# driver0-3.net
KiCad netlist of a schematic drawn in Altium Designer
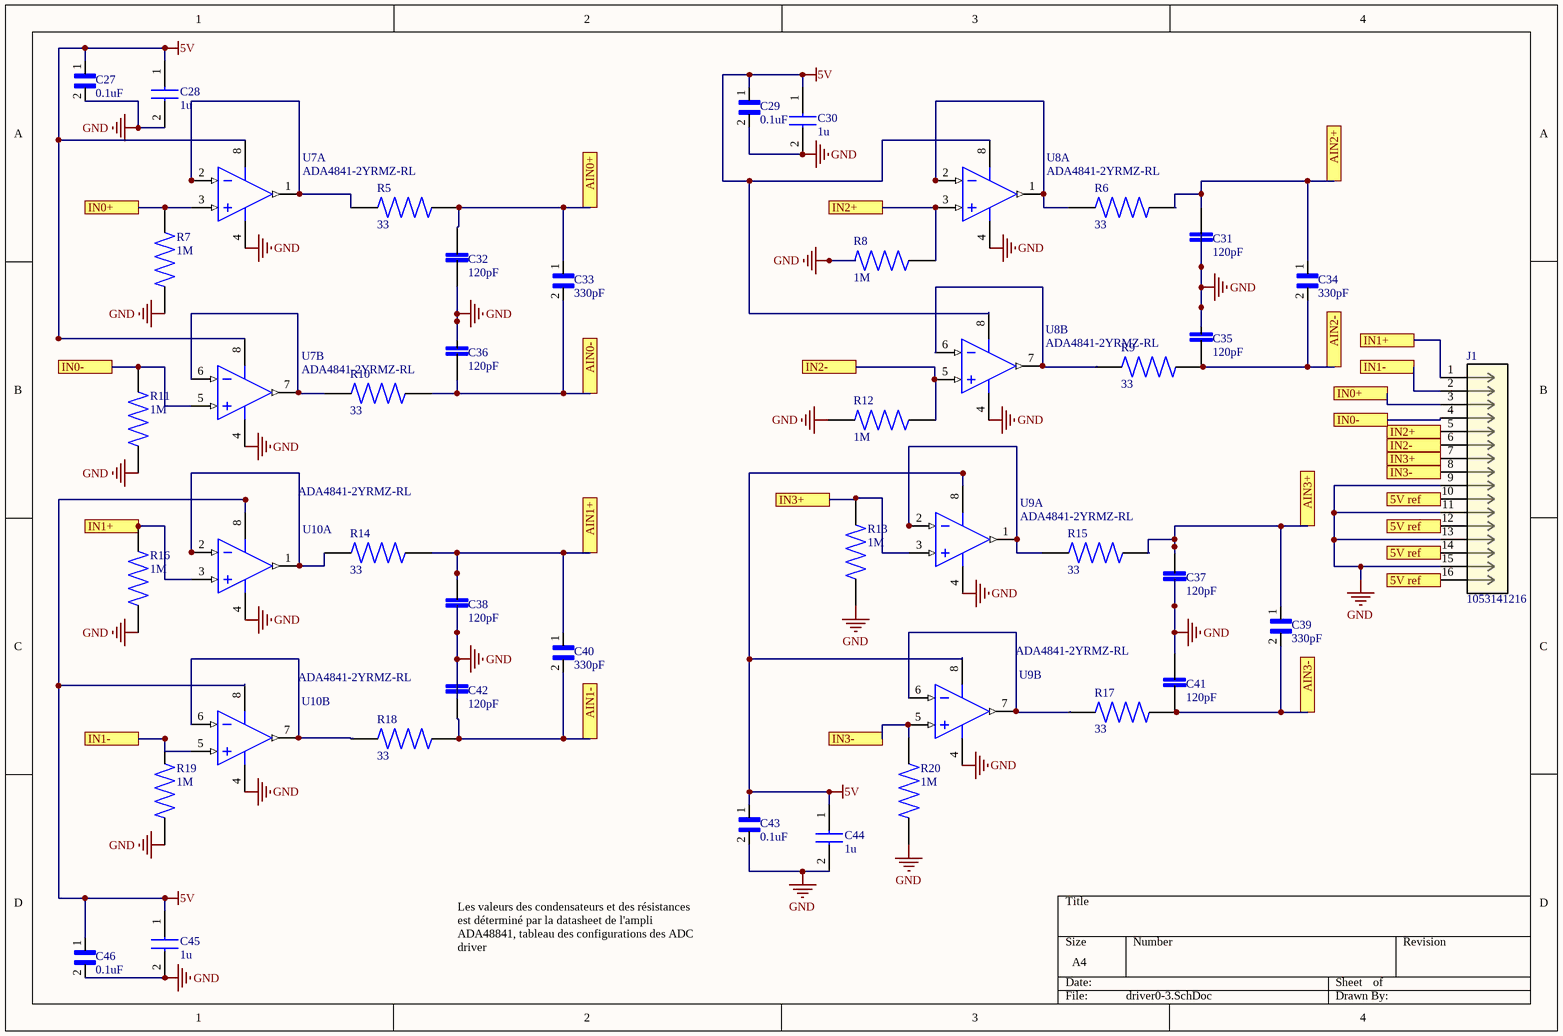
[diagram p0: driver0-3.SchDoc]

(export (version "E")
  (design (tool "Eeschema 10.0.6"))
  (components
    (comp (ref "C27")
      (value "0.1uF")
      (footprint "CAPC1608X90N")
      (description "Cap Ceramic 0.1uF 25V X5R 10% SMD 0603 85ÂÂŽ T/R")
      (fields
        (field (name "MP") "06033D104KAT2A")
        (field (name "MF") "{'manufacturer': u'AVX'}")
        (field (name "SOURCE") "workerBoard.SCHLIB")
      )
      (libsource (lib "GIGUL") (part "06033D104KAT2A"))
    )
    (comp (ref "C28")
      (value "1u")
      (footprint "CAPC1608X90N")
      (description "Capacitor")
      (fields
        (field (name "MANUFACTURER_PART_NUMBER") "0603YC105MAT4A")
        (field (name "SOURCE") "workerBoard.SCHLIB")
      )
      (libsource (lib "GIGUL") (part "0603YC105MAT4A"))
    )
    (comp (ref "C29")
      (value "0.1uF")
      (footprint "CAPC1608X90N")
      (description "Cap Ceramic 0.1uF 25V X5R 10% SMD 0603 85ÂÂŽ T/R")
      (fields
        (field (name "MP") "06033D104KAT2A")
        (field (name "MF") "{'manufacturer': u'AVX'}")
        (field (name "SOURCE") "workerBoard.SCHLIB")
      )
      (libsource (lib "GIGUL") (part "06033D104KAT2A"))
    )
    (comp (ref "C30")
      (value "1u")
      (footprint "CAPC1608X90N")
      (description "Capacitor")
      (fields
        (field (name "MANUFACTURER_PART_NUMBER") "0603YC105MAT4A")
        (field (name "SOURCE") "workerBoard.SCHLIB")
      )
      (libsource (lib "GIGUL") (part "0603YC105MAT4A"))
    )
    (comp (ref "C31")
      (value "120pF")
      (footprint "CAPC1608X90")
      (description "0603 120 pF 50 V Â±2 % Tolerance C0G/NP0 SMT Multilayer Ceramic Capacitor")
      (fields
        (field (name "MP") "06035A121GAT2A")
        (field (name "MF") "{'manufacturer': u'AVX'}")
        (field (name "SOURCE") "workerBoard.SCHLIB")
      )
      (libsource (lib "GIGUL") (part "06035A121GAT2A"))
    )
    (comp (ref "C32")
      (value "120pF")
      (footprint "CAPC1608X90")
      (description "0603 120 pF 50 V Â±2 % Tolerance C0G/NP0 SMT Multilayer Ceramic Capacitor")
      (fields
        (field (name "MP") "06035A121GAT2A")
        (field (name "MF") "{'manufacturer': u'AVX'}")
        (field (name "SOURCE") "workerBoard.SCHLIB")
      )
      (libsource (lib "GIGUL") (part "06035A121GAT2A"))
    )
    (comp (ref "C33")
      (value "330pF")
      (footprint "CAPC1608X90")
      (description "0603 SMD Ceramic Capacitors 0603 330pF 25volts C0G 2%")
      (fields
        (field (name "MP") "06033A331GAT2A")
        (field (name "MF") "{'manufacturer': u'AVX'}")
        (field (name "SOURCE") "workerBoard.SCHLIB")
      )
      (libsource (lib "") (part "Symbol_1"))
    )
    (comp (ref "C34")
      (value "330pF")
      (footprint "CAPC1608X90")
      (description "0603 SMD Ceramic Capacitors 0603 330pF 25volts C0G 2%")
      (fields
        (field (name "MP") "06033A331GAT2A")
        (field (name "MF") "{'manufacturer': u'AVX'}")
        (field (name "SOURCE") "workerBoard.SCHLIB")
      )
      (libsource (lib "") (part "Symbol_1"))
    )
    (comp (ref "C35")
      (value "120pF")
      (footprint "CAPC1608X90")
      (description "0603 120 pF 50 V Â±2 % Tolerance C0G/NP0 SMT Multilayer Ceramic Capacitor")
      (fields
        (field (name "MP") "06035A121GAT2A")
        (field (name "MF") "{'manufacturer': u'AVX'}")
        (field (name "SOURCE") "workerBoard.SCHLIB")
      )
      (libsource (lib "GIGUL") (part "06035A121GAT2A"))
    )
    (comp (ref "C36")
      (value "120pF")
      (footprint "CAPC1608X90")
      (description "0603 120 pF 50 V Â±2 % Tolerance C0G/NP0 SMT Multilayer Ceramic Capacitor")
      (fields
        (field (name "MP") "06035A121GAT2A")
        (field (name "MF") "{'manufacturer': u'AVX'}")
        (field (name "SOURCE") "workerBoard.SCHLIB")
      )
      (libsource (lib "GIGUL") (part "06035A121GAT2A"))
    )
    (comp (ref "C37")
      (value "120pF")
      (footprint "CAPC1608X90")
      (description "0603 120 pF 50 V Â±2 % Tolerance C0G/NP0 SMT Multilayer Ceramic Capacitor")
      (fields
        (field (name "MP") "06035A121GAT2A")
        (field (name "MF") "{'manufacturer': u'AVX'}")
        (field (name "SOURCE") "workerBoard.SCHLIB")
      )
      (libsource (lib "GIGUL") (part "06035A121GAT2A"))
    )
    (comp (ref "C38")
      (value "120pF")
      (footprint "CAPC1608X90")
      (description "0603 120 pF 50 V Â±2 % Tolerance C0G/NP0 SMT Multilayer Ceramic Capacitor")
      (fields
        (field (name "MP") "06035A121GAT2A")
        (field (name "MF") "{'manufacturer': u'AVX'}")
        (field (name "SOURCE") "workerBoard.SCHLIB")
      )
      (libsource (lib "GIGUL") (part "06035A121GAT2A"))
    )
    (comp (ref "C39")
      (value "330pF")
      (footprint "CAPC1608X90")
      (description "0603 SMD Ceramic Capacitors 0603 330pF 25volts C0G 2%")
      (fields
        (field (name "MP") "06033A331GAT2A")
        (field (name "MF") "{'manufacturer': u'AVX'}")
        (field (name "SOURCE") "workerBoard.SCHLIB")
      )
      (libsource (lib "") (part "Symbol_1"))
    )
    (comp (ref "C40")
      (value "330pF")
      (footprint "CAPC1608X90")
      (description "0603 SMD Ceramic Capacitors 0603 330pF 25volts C0G 2%")
      (fields
        (field (name "MP") "06033A331GAT2A")
        (field (name "MF") "{'manufacturer': u'AVX'}")
        (field (name "SOURCE") "workerBoard.SCHLIB")
      )
      (libsource (lib "") (part "Symbol_1"))
    )
    (comp (ref "C41")
      (value "120pF")
      (footprint "CAPC1608X90")
      (description "0603 120 pF 50 V Â±2 % Tolerance C0G/NP0 SMT Multilayer Ceramic Capacitor")
      (fields
        (field (name "MP") "06035A121GAT2A")
        (field (name "MF") "{'manufacturer': u'AVX'}")
        (field (name "SOURCE") "workerBoard.SCHLIB")
      )
      (libsource (lib "GIGUL") (part "06035A121GAT2A"))
    )
    (comp (ref "C42")
      (value "120pF")
      (footprint "CAPC1608X90")
      (description "0603 120 pF 50 V Â±2 % Tolerance C0G/NP0 SMT Multilayer Ceramic Capacitor")
      (fields
        (field (name "MP") "06035A121GAT2A")
        (field (name "MF") "{'manufacturer': u'AVX'}")
        (field (name "SOURCE") "workerBoard.SCHLIB")
      )
      (libsource (lib "GIGUL") (part "06035A121GAT2A"))
    )
    (comp (ref "C43")
      (value "0.1uF")
      (footprint "CAPC1608X90N")
      (description "Cap Ceramic 0.1uF 25V X5R 10% SMD 0603 85ÂÂŽ T/R")
      (fields
        (field (name "MP") "06033D104KAT2A")
        (field (name "MF") "{'manufacturer': u'AVX'}")
        (field (name "SOURCE") "workerBoard.SCHLIB")
      )
      (libsource (lib "GIGUL") (part "06033D104KAT2A"))
    )
    (comp (ref "C44")
      (value "1u")
      (footprint "CAPC1608X90N")
      (description "Capacitor")
      (fields
        (field (name "MANUFACTURER_PART_NUMBER") "0603YC105MAT4A")
        (field (name "SOURCE") "workerBoard.SCHLIB")
      )
      (libsource (lib "GIGUL") (part "0603YC105MAT4A"))
    )
    (comp (ref "C45")
      (value "1u")
      (footprint "CAPC1608X90N")
      (description "Capacitor")
      (fields
        (field (name "MANUFACTURER_PART_NUMBER") "0603YC105MAT4A")
        (field (name "SOURCE") "workerBoard.SCHLIB")
      )
      (libsource (lib "GIGUL") (part "0603YC105MAT4A"))
    )
    (comp (ref "C46")
      (value "0.1uF")
      (footprint "CAPC1608X90N")
      (description "Cap Ceramic 0.1uF 25V X5R 10% SMD 0603 85ÂÂŽ T/R")
      (fields
        (field (name "MP") "06033D104KAT2A")
        (field (name "MF") "{'manufacturer': u'AVX'}")
        (field (name "SOURCE") "workerBoard.SCHLIB")
      )
      (libsource (lib "GIGUL") (part "06033D104KAT2A"))
    )
    (comp (ref "J1")
      (value "1053141216")
      (footprint "CON_1053141216")
      (description "No Description Available")
      (fields
        (field (name "COPYRIGHT") "Copyright (C) 2021 Ultra Librarian. All rights reserved.")
        (field (name "SOURCE") "workerBoard.SCHLIB")
      )
      (libsource (lib "GIGUL") (part "1053141216"))
    )
    (comp (ref "R5")
      (value "33")
      (footprint "RESC1608X55N")
      (description "RES SMD 33 OHM 0.1% 1/10W 0603")
      (fields
        (field (name "MP") "RT0603BRD0733RL")
        (field (name "MF") "{'manufacturer': u'Yageo'}")
        (field (name "SOURCE") "workerBoard.SCHLIB")
      )
      (libsource (lib "GIGUL") (part "Symbol"))
    )
    (comp (ref "R6")
      (value "33")
      (footprint "RESC1608X55N")
      (description "RES SMD 33 OHM 0.1% 1/10W 0603")
      (fields
        (field (name "MP") "RT0603BRD0733RL")
        (field (name "MF") "{'manufacturer': u'Yageo'}")
        (field (name "SOURCE") "workerBoard.SCHLIB")
      )
      (libsource (lib "GIGUL") (part "Symbol"))
    )
    (comp (ref "R7")
      (value "1M")
      (footprint "RESC1608X55N")
      (fields
        (field (name "MP") "RT0603DRD071ML")
        (field (name "MF") "{'manufacturer': u'Yageo'}")
        (field (name "SOURCE") "workerBoard.SCHLIB")
      )
      (libsource (lib "GIGUL") (part "Symbol"))
    )
    (comp (ref "R8")
      (value "1M")
      (footprint "RESC1608X55N")
      (fields
        (field (name "MP") "RT0603DRD071ML")
        (field (name "MF") "{'manufacturer': u'Yageo'}")
        (field (name "SOURCE") "workerBoard.SCHLIB")
      )
      (libsource (lib "GIGUL") (part "Symbol"))
    )
    (comp (ref "R9")
      (value "33")
      (footprint "RESC1608X55N")
      (description "RES SMD 33 OHM 0.1% 1/10W 0603")
      (fields
        (field (name "MP") "RT0603BRD0733RL")
        (field (name "MF") "{'manufacturer': u'Yageo'}")
        (field (name "SOURCE") "workerBoard.SCHLIB")
      )
      (libsource (lib "GIGUL") (part "Symbol"))
    )
    (comp (ref "R10")
      (value "33")
      (footprint "RESC1608X55N")
      (description "RES SMD 33 OHM 0.1% 1/10W 0603")
      (fields
        (field (name "MP") "RT0603BRD0733RL")
        (field (name "MF") "{'manufacturer': u'Yageo'}")
        (field (name "SOURCE") "workerBoard.SCHLIB")
      )
      (libsource (lib "GIGUL") (part "Symbol"))
    )
    (comp (ref "R11")
      (value "1M")
      (footprint "RESC1608X55N")
      (fields
        (field (name "MP") "RT0603DRD071ML")
        (field (name "MF") "{'manufacturer': u'Yageo'}")
        (field (name "SOURCE") "workerBoard.SCHLIB")
      )
      (libsource (lib "GIGUL") (part "Symbol"))
    )
    (comp (ref "R12")
      (value "1M")
      (footprint "RESC1608X55N")
      (fields
        (field (name "MP") "RT0603DRD071ML")
        (field (name "MF") "{'manufacturer': u'Yageo'}")
        (field (name "SOURCE") "workerBoard.SCHLIB")
      )
      (libsource (lib "GIGUL") (part "Symbol"))
    )
    (comp (ref "R13")
      (value "1M")
      (footprint "RESC1608X55N")
      (fields
        (field (name "MP") "RT0603DRD071ML")
        (field (name "MF") "{'manufacturer': u'Yageo'}")
        (field (name "SOURCE") "workerBoard.SCHLIB")
      )
      (libsource (lib "GIGUL") (part "Symbol"))
    )
    (comp (ref "R14")
      (value "33")
      (footprint "RESC1608X55N")
      (description "RES SMD 33 OHM 0.1% 1/10W 0603")
      (fields
        (field (name "MP") "RT0603BRD0733RL")
        (field (name "MF") "{'manufacturer': u'Yageo'}")
        (field (name "SOURCE") "workerBoard.SCHLIB")
      )
      (libsource (lib "GIGUL") (part "Symbol"))
    )
    (comp (ref "R15")
      (value "33")
      (footprint "RESC1608X55N")
      (description "RES SMD 33 OHM 0.1% 1/10W 0603")
      (fields
        (field (name "MP") "RT0603BRD0733RL")
        (field (name "MF") "{'manufacturer': u'Yageo'}")
        (field (name "SOURCE") "workerBoard.SCHLIB")
      )
      (libsource (lib "GIGUL") (part "Symbol"))
    )
    (comp (ref "R16")
      (value "1M")
      (footprint "RESC1608X55N")
      (fields
        (field (name "MP") "RT0603DRD071ML")
        (field (name "MF") "{'manufacturer': u'Yageo'}")
        (field (name "SOURCE") "workerBoard.SCHLIB")
      )
      (libsource (lib "GIGUL") (part "Symbol"))
    )
    (comp (ref "R17")
      (value "33")
      (footprint "RESC1608X55N")
      (description "RES SMD 33 OHM 0.1% 1/10W 0603")
      (fields
        (field (name "MP") "RT0603BRD0733RL")
        (field (name "MF") "{'manufacturer': u'Yageo'}")
        (field (name "SOURCE") "workerBoard.SCHLIB")
      )
      (libsource (lib "GIGUL") (part "Symbol"))
    )
    (comp (ref "R18")
      (value "33")
      (footprint "RESC1608X55N")
      (description "RES SMD 33 OHM 0.1% 1/10W 0603")
      (fields
        (field (name "MP") "RT0603BRD0733RL")
        (field (name "MF") "{'manufacturer': u'Yageo'}")
        (field (name "SOURCE") "workerBoard.SCHLIB")
      )
      (libsource (lib "GIGUL") (part "Symbol"))
    )
    (comp (ref "R19")
      (value "1M")
      (footprint "RESC1608X55N")
      (fields
        (field (name "MP") "RT0603DRD071ML")
        (field (name "MF") "{'manufacturer': u'Yageo'}")
        (field (name "SOURCE") "workerBoard.SCHLIB")
      )
      (libsource (lib "GIGUL") (part "Symbol"))
    )
    (comp (ref "R20")
      (value "1M")
      (footprint "RESC1608X55N")
      (fields
        (field (name "MP") "RT0603DRD071ML")
        (field (name "MF") "{'manufacturer': u'Yageo'}")
        (field (name "SOURCE") "workerBoard.SCHLIB")
      )
      (libsource (lib "GIGUL") (part "Symbol"))
    )
    (comp (ref "U7")
      (value "ADA4841-2YRMZ-RL")
      (footprint "ADI-RM-8_M")
      (fields
        (field (name "MANUFACTURER") "Analog Devices")
        (field (name "GENERIC PART NUMBER") "ADA4841-2")
        (field (name "SOURCE") "workerBoard.SCHLIB")
      )
      (libsource (lib "GIGUL") (part "CMP-0384-01677-1"))
    )
    (comp (ref "U8")
      (value "ADA4841-2YRMZ-RL")
      (footprint "ADI-RM-8_M")
      (fields
        (field (name "MANUFACTURER") "Analog Devices")
        (field (name "GENERIC PART NUMBER") "ADA4841-2")
        (field (name "SOURCE") "workerBoard.SCHLIB")
      )
      (libsource (lib "GIGUL") (part "CMP-0384-01677-1"))
    )
    (comp (ref "U9")
      (value "ADA4841-2YRMZ-RL")
      (footprint "ADI-RM-8_M")
      (fields
        (field (name "MANUFACTURER") "Analog Devices")
        (field (name "GENERIC PART NUMBER") "ADA4841-2")
        (field (name "SOURCE") "workerBoard.SCHLIB")
      )
      (libsource (lib "GIGUL") (part "CMP-0384-01677-1"))
    )
    (comp (ref "U10")
      (value "ADA4841-2YRMZ-RL")
      (footprint "ADI-RM-8_M")
      (fields
        (field (name "MANUFACTURER") "Analog Devices")
        (field (name "GENERIC PART NUMBER") "ADA4841-2")
        (field (name "SOURCE") "workerBoard.SCHLIB")
      )
      (libsource (lib "GIGUL") (part "CMP-0384-01677-1"))
    )
  )
  (nets
    (net (code "1") (name "/5V ref") (class "Default")
      (node (ref "J1") (pin "10") (pinfunction "10_10") (pintype "passive"))
      (node (ref "J1") (pin "12") (pinfunction "12_12") (pintype "passive"))
      (node (ref "J1") (pin "14") (pinfunction "14_14") (pintype "passive"))
      (node (ref "J1") (pin "16") (pinfunction "16_16") (pintype "passive"))
    )
    (net (code "2") (name "/AIN0+") (class "Default")
      (node (ref "C32") (pin "2") (pinfunction "2_2") (pintype "passive"))
      (node (ref "C33") (pin "1") (pinfunction "1_1") (pintype "passive"))
      (node (ref "R5") (pin "2") (pinfunction "2_2") (pintype "passive"))
    )
    (net (code "3") (name "/AIN0-") (class "Default")
      (node (ref "C33") (pin "2") (pinfunction "2_2") (pintype "passive"))
      (node (ref "C36") (pin "1") (pinfunction "1_1") (pintype "passive"))
      (node (ref "R10") (pin "2") (pinfunction "2_2") (pintype "passive"))
    )
    (net (code "4") (name "/AIN1+") (class "Default")
      (node (ref "C38") (pin "2") (pinfunction "2_2") (pintype "passive"))
      (node (ref "C40") (pin "1") (pinfunction "1_1") (pintype "passive"))
      (node (ref "R14") (pin "2") (pinfunction "2_2") (pintype "passive"))
    )
    (net (code "5") (name "/AIN1-") (class "Default")
      (node (ref "C40") (pin "2") (pinfunction "2_2") (pintype "passive"))
      (node (ref "C42") (pin "1") (pinfunction "1_1") (pintype "passive"))
      (node (ref "R18") (pin "2") (pinfunction "2_2") (pintype "passive"))
    )
    (net (code "6") (name "/AIN2+") (class "Default")
      (node (ref "C31") (pin "2") (pinfunction "2_2") (pintype "passive"))
      (node (ref "C34") (pin "1") (pinfunction "1_1") (pintype "passive"))
      (node (ref "R6") (pin "2") (pinfunction "2_2") (pintype "passive"))
    )
    (net (code "7") (name "/AIN2-") (class "Default")
      (node (ref "C34") (pin "2") (pinfunction "2_2") (pintype "passive"))
      (node (ref "C35") (pin "1") (pinfunction "1_1") (pintype "passive"))
      (node (ref "R9") (pin "2") (pinfunction "2_2") (pintype "passive"))
    )
    (net (code "8") (name "/AIN3+") (class "Default")
      (node (ref "C37") (pin "2") (pinfunction "2_2") (pintype "passive"))
      (node (ref "C39") (pin "1") (pinfunction "1_1") (pintype "passive"))
      (node (ref "R15") (pin "2") (pinfunction "2_2") (pintype "passive"))
    )
    (net (code "9") (name "/AIN3-") (class "Default")
      (node (ref "C39") (pin "2") (pinfunction "2_2") (pintype "passive"))
      (node (ref "C41") (pin "1") (pinfunction "1_1") (pintype "passive"))
      (node (ref "R17") (pin "2") (pinfunction "2_2") (pintype "passive"))
    )
    (net (code "10") (name "/IN0+") (class "Default")
      (node (ref "J1") (pin "3") (pinfunction "3_3") (pintype "passive"))
      (node (ref "R7") (pin "2") (pinfunction "2_2") (pintype "passive"))
      (node (ref "U7") (pin "3") (pinfunction "+IN_1_3") (pintype "input"))
    )
    (net (code "11") (name "/IN0-") (class "Default")
      (node (ref "J1") (pin "4") (pinfunction "4_4") (pintype "passive"))
      (node (ref "R11") (pin "2") (pinfunction "2_2") (pintype "passive"))
      (node (ref "U7") (pin "5") (pinfunction "+IN_2_5") (pintype "input"))
    )
    (net (code "12") (name "/IN1+") (class "Default")
      (node (ref "J1") (pin "1") (pinfunction "1_1") (pintype "passive"))
      (node (ref "R16") (pin "2") (pinfunction "2_2") (pintype "passive"))
      (node (ref "U10") (pin "3") (pinfunction "+IN_1_3") (pintype "input"))
    )
    (net (code "13") (name "/IN1-") (class "Default")
      (node (ref "J1") (pin "2") (pinfunction "2_2") (pintype "passive"))
      (node (ref "R19") (pin "2") (pinfunction "2_2") (pintype "passive"))
      (node (ref "U10") (pin "5") (pinfunction "+IN_2_5") (pintype "input"))
    )
    (net (code "14") (name "/IN2+") (class "Default")
      (node (ref "J1") (pin "5") (pinfunction "5_5") (pintype "passive"))
      (node (ref "R8") (pin "1") (pinfunction "1_1") (pintype "passive"))
      (node (ref "U8") (pin "3") (pinfunction "+IN_1_3") (pintype "input"))
    )
    (net (code "15") (name "/IN2-") (class "Default")
      (node (ref "J1") (pin "6") (pinfunction "6_6") (pintype "passive"))
      (node (ref "R12") (pin "1") (pinfunction "1_1") (pintype "passive"))
      (node (ref "U8") (pin "5") (pinfunction "+IN_2_5") (pintype "input"))
    )
    (net (code "16") (name "/IN3+") (class "Default")
      (node (ref "J1") (pin "7") (pinfunction "7_7") (pintype "passive"))
      (node (ref "R13") (pin "2") (pinfunction "2_2") (pintype "passive"))
      (node (ref "U9") (pin "3") (pinfunction "+IN_1_3") (pintype "input"))
    )
    (net (code "17") (name "/IN3-") (class "Default")
      (node (ref "J1") (pin "8") (pinfunction "8_8") (pintype "passive"))
      (node (ref "R20") (pin "2") (pinfunction "2_2") (pintype "passive"))
      (node (ref "U9") (pin "5") (pinfunction "+IN_2_5") (pintype "input"))
    )
    (net (code "18") (name "5V") (class "Default")
      (node (ref "C27") (pin "1") (pinfunction "1_1") (pintype "passive"))
      (node (ref "C28") (pin "1") (pinfunction "1_1") (pintype "passive"))
      (node (ref "C29") (pin "1") (pinfunction "1_1") (pintype "passive"))
      (node (ref "C30") (pin "1") (pinfunction "1_1") (pintype "passive"))
      (node (ref "C43") (pin "1") (pinfunction "1_1") (pintype "passive"))
      (node (ref "C44") (pin "1") (pinfunction "1_1") (pintype "passive"))
      (node (ref "C45") (pin "1") (pinfunction "1_1") (pintype "passive"))
      (node (ref "C46") (pin "1") (pinfunction "1_1") (pintype "passive"))
      (node (ref "U10") (pin "8") (pinfunction "+VS_8") (pintype "power_in"))
      (node (ref "U7") (pin "8") (pinfunction "+VS_8") (pintype "power_in"))
      (node (ref "U8") (pin "8") (pinfunction "+VS_8") (pintype "power_in"))
      (node (ref "U9") (pin "8") (pinfunction "+VS_8") (pintype "power_in"))
    )
    (net (code "19") (name "GND") (class "Default")
      (node (ref "C27") (pin "2") (pinfunction "2_2") (pintype "passive"))
      (node (ref "C28") (pin "2") (pinfunction "2_2") (pintype "passive"))
      (node (ref "C29") (pin "2") (pinfunction "2_2") (pintype "passive"))
      (node (ref "C30") (pin "2") (pinfunction "2_2") (pintype "passive"))
      (node (ref "C31") (pin "1") (pinfunction "1_1") (pintype "passive"))
      (node (ref "C32") (pin "1") (pinfunction "1_1") (pintype "passive"))
      (node (ref "C35") (pin "2") (pinfunction "2_2") (pintype "passive"))
      (node (ref "C36") (pin "2") (pinfunction "2_2") (pintype "passive"))
      (node (ref "C37") (pin "1") (pinfunction "1_1") (pintype "passive"))
      (node (ref "C38") (pin "1") (pinfunction "1_1") (pintype "passive"))
      (node (ref "C41") (pin "2") (pinfunction "2_2") (pintype "passive"))
      (node (ref "C42") (pin "2") (pinfunction "2_2") (pintype "passive"))
      (node (ref "C43") (pin "2") (pinfunction "2_2") (pintype "passive"))
      (node (ref "C44") (pin "2") (pinfunction "2_2") (pintype "passive"))
      (node (ref "C45") (pin "2") (pinfunction "2_2") (pintype "passive"))
      (node (ref "C46") (pin "2") (pinfunction "2_2") (pintype "passive"))
      (node (ref "J1") (pin "11") (pinfunction "11_11") (pintype "passive"))
      (node (ref "J1") (pin "13") (pinfunction "13_13") (pintype "passive"))
      (node (ref "J1") (pin "15") (pinfunction "15_15") (pintype "passive"))
      (node (ref "J1") (pin "9") (pinfunction "9_9") (pintype "passive"))
      (node (ref "R11") (pin "1") (pinfunction "1_1") (pintype "passive"))
      (node (ref "R12") (pin "2") (pinfunction "2_2") (pintype "passive"))
      (node (ref "R13") (pin "1") (pinfunction "1_1") (pintype "passive"))
      (node (ref "R16") (pin "1") (pinfunction "1_1") (pintype "passive"))
      (node (ref "R19") (pin "1") (pinfunction "1_1") (pintype "passive"))
      (node (ref "R20") (pin "1") (pinfunction "1_1") (pintype "passive"))
      (node (ref "R7") (pin "1") (pinfunction "1_1") (pintype "passive"))
      (node (ref "R8") (pin "2") (pinfunction "2_2") (pintype "passive"))
      (node (ref "U10") (pin "4") (pinfunction "-VS_4") (pintype "power_in"))
      (node (ref "U7") (pin "4") (pinfunction "-VS_4") (pintype "power_in"))
      (node (ref "U8") (pin "4") (pinfunction "-VS_4") (pintype "power_in"))
      (node (ref "U9") (pin "4") (pinfunction "-VS_4") (pintype "power_in"))
    )
    (net (code "20") (name "Net-(U7A--IN_1)") (class "Default")
      (node (ref "R5") (pin "1") (pinfunction "1_1") (pintype "passive"))
      (node (ref "U7") (pin "1") (pinfunction "OUT_1_1") (pintype "output"))
      (node (ref "U7") (pin "2") (pinfunction "-IN_1_2") (pintype "input"))
    )
    (net (code "21") (name "Net-(U7B--IN_2)") (class "Default")
      (node (ref "R10") (pin "1") (pinfunction "1_1") (pintype "passive"))
      (node (ref "U7") (pin "6") (pinfunction "-IN_2_6") (pintype "input"))
      (node (ref "U7") (pin "7") (pinfunction "OUT_2_7") (pintype "output"))
    )
    (net (code "22") (name "Net-(U8A--IN_1)") (class "Default")
      (node (ref "R6") (pin "1") (pinfunction "1_1") (pintype "passive"))
      (node (ref "U8") (pin "1") (pinfunction "OUT_1_1") (pintype "output"))
      (node (ref "U8") (pin "2") (pinfunction "-IN_1_2") (pintype "input"))
    )
    (net (code "23") (name "Net-(U8B--IN_2)") (class "Default")
      (node (ref "R9") (pin "1") (pinfunction "1_1") (pintype "passive"))
      (node (ref "U8") (pin "6") (pinfunction "-IN_2_6") (pintype "input"))
      (node (ref "U8") (pin "7") (pinfunction "OUT_2_7") (pintype "output"))
    )
    (net (code "24") (name "Net-(U9A--IN_1)") (class "Default")
      (node (ref "R15") (pin "1") (pinfunction "1_1") (pintype "passive"))
      (node (ref "U9") (pin "1") (pinfunction "OUT_1_1") (pintype "output"))
      (node (ref "U9") (pin "2") (pinfunction "-IN_1_2") (pintype "input"))
    )
    (net (code "25") (name "Net-(U9B--IN_2)") (class "Default")
      (node (ref "R17") (pin "1") (pinfunction "1_1") (pintype "passive"))
      (node (ref "U9") (pin "6") (pinfunction "-IN_2_6") (pintype "input"))
      (node (ref "U9") (pin "7") (pinfunction "OUT_2_7") (pintype "output"))
    )
    (net (code "26") (name "Net-(U10A--IN_1)") (class "Default")
      (node (ref "R14") (pin "1") (pinfunction "1_1") (pintype "passive"))
      (node (ref "U10") (pin "1") (pinfunction "OUT_1_1") (pintype "output"))
      (node (ref "U10") (pin "2") (pinfunction "-IN_1_2") (pintype "input"))
    )
    (net (code "27") (name "Net-(U10B--IN_2)") (class "Default")
      (node (ref "R18") (pin "1") (pinfunction "1_1") (pintype "passive"))
      (node (ref "U10") (pin "6") (pinfunction "-IN_2_6") (pintype "input"))
      (node (ref "U10") (pin "7") (pinfunction "OUT_2_7") (pintype "output"))
    )
  )
)
